# RS232_Prog_Conn_Adapter.net
KiCad netlist of a schematic drawn in EAGLE
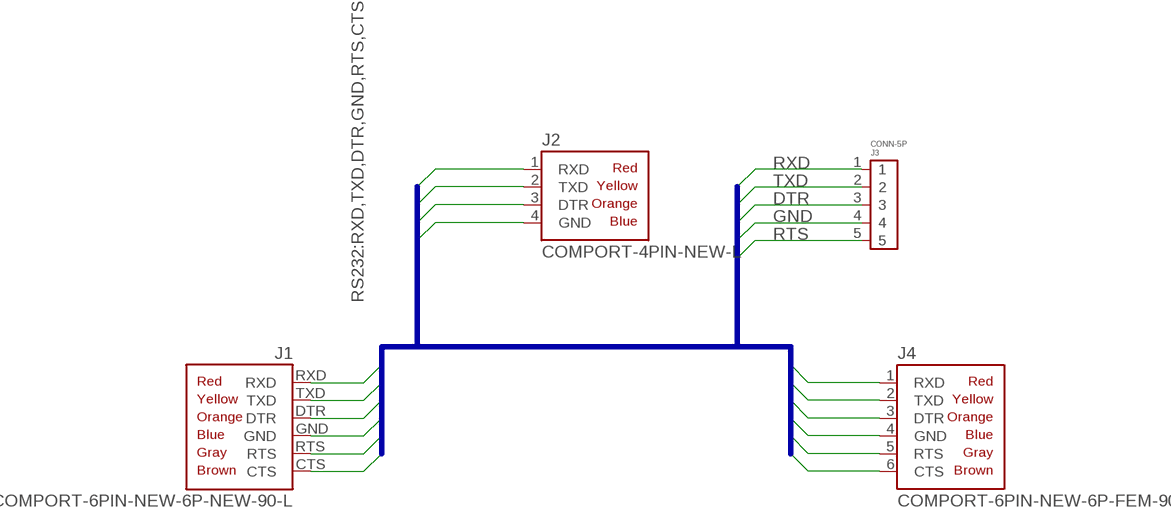
[diagram p0: schematic, sheet 1]

(export (version "E")
  (design (tool "Eeschema 10.0.6"))
  (components
    (comp (ref "J1")
      (value "COMPORT-6PIN-NEW-6P-NEW-90-L")
      (footprint "eagle-import:RS232-6PIN-NEW-90-L")
      (libsource (lib "eagle-import") (part "COMPORT-6PIN-NEW-6P-NEW-90-L"))
    )
    (comp (ref "J2")
      (value "COMPORT-4PIN-NEW-L")
      (footprint "eagle-import:RS232-4PIN-NEW-L")
      (libsource (lib "eagle-import") (part "COMPORT-4PIN-NEW-L"))
    )
    (comp (ref "J3")
      (value "CONN-5P")
      (footprint "eagle-import:CONN-5P-N")
      (libsource (lib "eagle-import") (part "CONN-5P"))
    )
    (comp (ref "J4")
      (value "COMPORT-6PIN-NEW-6P-FEM-90")
      (footprint "eagle-import:CONN-6P-FEM-90")
      (libsource (lib "eagle-import") (part "COMPORT-6PIN-NEW-6P-FEM-90"))
    )
  )
  (nets
    (net (code "2") (name "/CTS") (class "Default")
      (node (ref "J1") (pin "CTS") (pinfunction "CTS_CTS") (pintype "passive"))
      (node (ref "J4") (pin "6") (pinfunction "CTS_6") (pintype "passive"))
    )
    (net (code "3") (name "/DTR") (class "Default")
      (node (ref "J1") (pin "DTR") (pinfunction "DTR_DTR") (pintype "passive"))
      (node (ref "J2") (pin "3") (pinfunction "DTR_3") (pintype "passive"))
      (node (ref "J3") (pin "3") (pinfunction "3_3") (pintype "passive"))
      (node (ref "J4") (pin "3") (pinfunction "DTR_3") (pintype "passive"))
    )
    (net (code "4") (name "/GND") (class "Default")
      (node (ref "J1") (pin "GND") (pinfunction "GND_GND") (pintype "passive"))
      (node (ref "J2") (pin "4") (pinfunction "GND_4") (pintype "passive"))
      (node (ref "J3") (pin "4") (pinfunction "4_4") (pintype "passive"))
      (node (ref "J4") (pin "4") (pinfunction "GND_4") (pintype "passive"))
    )
    (net (code "5") (name "/RTS") (class "Default")
      (node (ref "J1") (pin "RTS") (pinfunction "RTS_RTS") (pintype "passive"))
      (node (ref "J3") (pin "5") (pinfunction "5_5") (pintype "passive"))
      (node (ref "J4") (pin "5") (pinfunction "RTS_5") (pintype "passive"))
    )
    (net (code "6") (name "/RXD") (class "Default")
      (node (ref "J1") (pin "RXD") (pinfunction "RXD_RXD") (pintype "passive"))
      (node (ref "J2") (pin "1") (pinfunction "RXD_1") (pintype "passive"))
      (node (ref "J3") (pin "1") (pinfunction "1_1") (pintype "passive"))
      (node (ref "J4") (pin "1") (pinfunction "RXD_1") (pintype "passive"))
    )
    (net (code "7") (name "/TXD") (class "Default")
      (node (ref "J1") (pin "TXD") (pinfunction "TXD_TXD") (pintype "passive"))
      (node (ref "J2") (pin "2") (pinfunction "TXD_2") (pintype "passive"))
      (node (ref "J3") (pin "2") (pinfunction "2_2") (pintype "passive"))
      (node (ref "J4") (pin "2") (pinfunction "TXD_2") (pintype "passive"))
    )
  )
)
